# LED_Driver_NE2R757GT-P6.net
KiCad netlist of a schematic drawn in Altium Designer
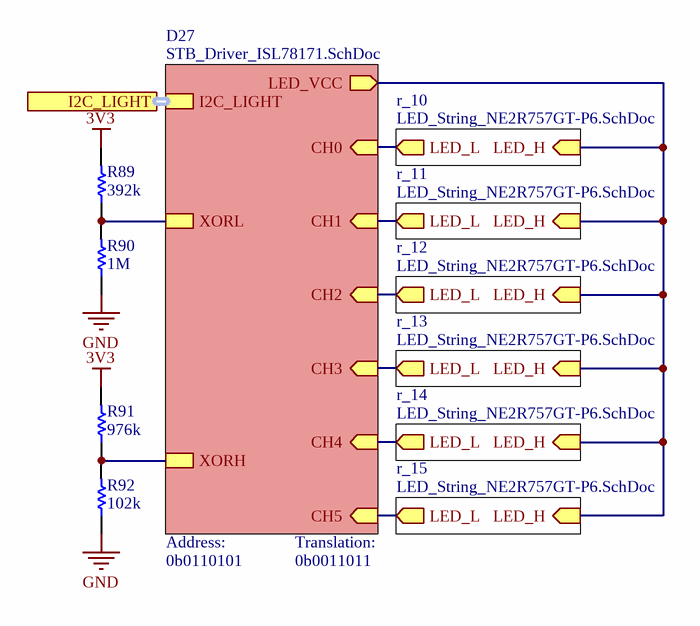
[diagram p0: LED_Driver_NE2R757GT-P6.SchDoc]

(export (version "E")
  (design (tool "Eeschema 10.0.6"))
  (components
    (comp (ref "R89")
      (value "392k")
      (footprint "RESC1005X40X25LL05T05")
      (fields
        (field (name "PART NUMBER") "ERJ-2RKF3923X")
        (field (name "MANUFACTURER") "Panasonic")
        (field (name "TOLERANCE") "1%")
      )
      (libsource (lib "Altium Content Vault") (part "RES"))
    )
    (comp (ref "R90")
      (value "1M")
      (footprint "RESC1005X40X25LL05T05")
      (description "Chip Resistor, 1 MOhm, +/- 1%, 100 mW, -55 to 155 degC, 0402 (1005 Metric), RoHS, Tape and Reel")
      (fields (field (name "PARTNUMBER") "ERJ-2RKF1004X") (field (name "TOLERANCE") "1%"))
      (libsource (lib "Altium Content Vault") (part "RES-2"))
    )
    (comp (ref "R91")
      (value "976k")
      (footprint "RESC1005X40X25LL05T05")
      (fields
        (field (name "MANUFACTURER") "Panasonic")
        (field (name "PART NUMBER") "ERJ-2RKF9763X")
        (field (name "TOLERANCE") "1%")
      )
      (libsource (lib "Altium Content Vault") (part "RES"))
    )
    (comp (ref "R92")
      (value "102k")
      (footprint "RESC1005X40X25LL05T05")
      (fields
        (field (name "MANUFACTURER") "Panasonic")
        (field (name "PART NUMBER") "ERJ-2RKF1023X")
        (field (name "TOLERANCE") "1%")
      )
      (libsource (lib "Altium Content Vault") (part "RES"))
    )
  )
  (nets
    (net (code "10") (name "/XORH") (class "Default")
      (node (ref "R91") (pin "1") (pinfunction "1_1") (pintype "passive"))
      (node (ref "R92") (pin "2") (pinfunction "2_2") (pintype "passive"))
    )
    (net (code "11") (name "/XORL") (class "Default")
      (node (ref "R89") (pin "1") (pinfunction "1_1") (pintype "passive"))
      (node (ref "R90") (pin "2") (pinfunction "2_2") (pintype "passive"))
    )
    (net (code "12") (name "3V3") (class "Default")
      (node (ref "R89") (pin "2") (pinfunction "2_2") (pintype "passive"))
      (node (ref "R91") (pin "2") (pinfunction "2_2") (pintype "passive"))
    )
    (net (code "13") (name "GND") (class "Default")
      (node (ref "R90") (pin "1") (pinfunction "1_1") (pintype "passive"))
      (node (ref "R92") (pin "1") (pinfunction "1_1") (pintype "passive"))
    )
  )
)
